# transmitter.net
KiCad netlist of a schematic drawn in EAGLE
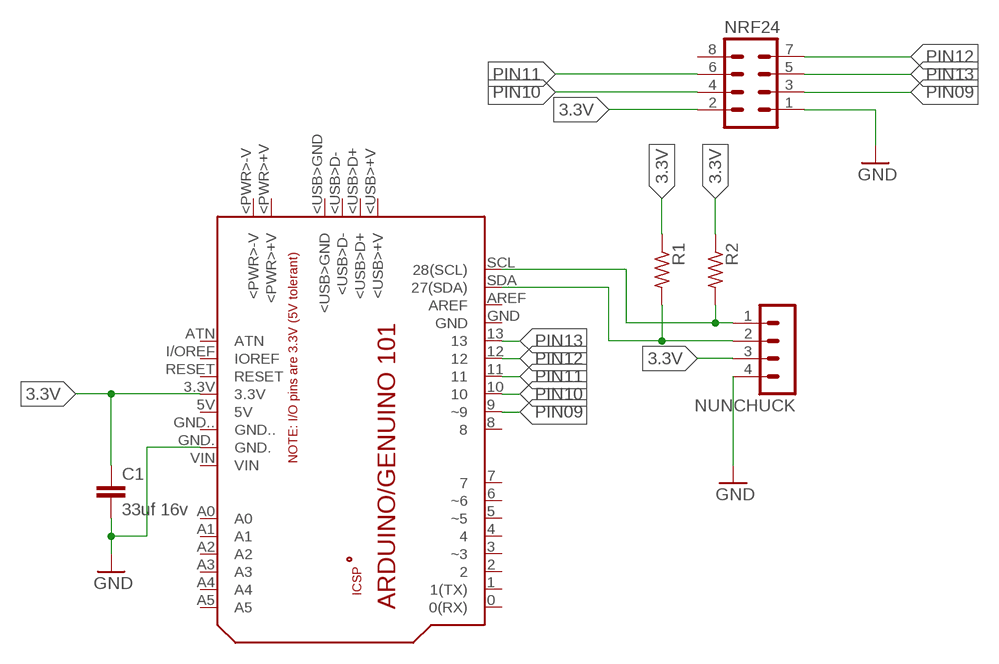
[diagram p0: schematic, sheet 1]

(export (version "E")
  (design (tool "Eeschema 10.0.6"))
  (components
    (comp (ref "C1")
      (value "33uf 16v")
      (footprint "eagle-import:C025-024X044")
      (libsource (lib "eagle-import") (part "C-EU025-024X044"))
    )
    (comp (ref "NRF24")
      (value "MA04-2")
      (footprint "eagle-import:MA04-2")
      (libsource (lib "eagle-import") (part "MA04-2"))
    )
    (comp (ref "NUNCHUCK")
      (value "MA04-1")
      (footprint "eagle-import:MA04-1")
      (libsource (lib "eagle-import") (part "MA04-1"))
    )
    (comp (ref "PCB1")
      (value "ARDUINO_101")
      (footprint "eagle-import:ARDUINO_101")
      (libsource (lib "eagle-import") (part "ARDUINO_101"))
    )
    (comp (ref "R1")
      (value "R-US_0204/2V")
      (footprint "eagle-import:0204V")
      (libsource (lib "eagle-import") (part "R-US_0204/2V"))
    )
    (comp (ref "R2")
      (value "R-US_0204/2V")
      (footprint "eagle-import:0204V")
      (libsource (lib "eagle-import") (part "R-US_0204/2V"))
    )
  )
  (nets
    (net (code "1") (name "3.3V") (class "Default")
      (node (ref "C1") (pin "1") (pinfunction "1_1") (pintype "passive"))
      (node (ref "NRF24") (pin "2") (pinfunction "2_2") (pintype "passive"))
      (node (ref "NUNCHUCK") (pin "3") (pinfunction "3_3") (pintype "passive"))
      (node (ref "PCB1") (pin "3.3V") (pinfunction "3.3V_3.3V") (pintype "bidirectional"))
      (node (ref "R1") (pin "1") (pinfunction "1_1") (pintype "passive"))
      (node (ref "R2") (pin "1") (pinfunction "1_1") (pintype "passive"))
    )
    (net (code "2") (name "GND") (class "Default")
      (node (ref "C1") (pin "2") (pinfunction "2_2") (pintype "passive"))
      (node (ref "NRF24") (pin "1") (pinfunction "1_1") (pintype "passive"))
      (node (ref "NUNCHUCK") (pin "4") (pinfunction "4_4") (pintype "passive"))
      (node (ref "PCB1") (pin "GND.") (pinfunction "GND._GND.") (pintype "bidirectional"))
    )
    (net (code "3") (name "Net-(PCB1-27(SDA))") (class "Default")
      (node (ref "NUNCHUCK") (pin "2") (pinfunction "2_2") (pintype "passive"))
      (node (ref "PCB1") (pin "SDA") (pinfunction "27(SDA)_SDA") (pintype "bidirectional"))
      (node (ref "R1") (pin "2") (pinfunction "2_2") (pintype "passive"))
    )
    (net (code "4") (name "Net-(PCB1-28(SCL))") (class "Default")
      (node (ref "NUNCHUCK") (pin "1") (pinfunction "1_1") (pintype "passive"))
      (node (ref "PCB1") (pin "SCL") (pinfunction "28(SCL)_SCL") (pintype "bidirectional"))
      (node (ref "R2") (pin "2") (pinfunction "2_2") (pintype "passive"))
    )
    (net (code "5") (name "PIN09") (class "Default")
      (node (ref "NRF24") (pin "3") (pinfunction "3_3") (pintype "passive"))
      (node (ref "PCB1") (pin "9") (pinfunction "~{9}_9") (pintype "bidirectional"))
    )
    (net (code "6") (name "PIN10") (class "Default")
      (node (ref "NRF24") (pin "4") (pinfunction "4_4") (pintype "passive"))
      (node (ref "PCB1") (pin "10") (pinfunction "10_10") (pintype "bidirectional"))
    )
    (net (code "7") (name "PIN11") (class "Default")
      (node (ref "NRF24") (pin "6") (pinfunction "6_6") (pintype "passive"))
      (node (ref "PCB1") (pin "11") (pinfunction "11_11") (pintype "bidirectional"))
    )
    (net (code "8") (name "PIN12") (class "Default")
      (node (ref "NRF24") (pin "7") (pinfunction "7_7") (pintype "passive"))
      (node (ref "PCB1") (pin "12") (pinfunction "12_12") (pintype "bidirectional"))
    )
    (net (code "9") (name "PIN13") (class "Default")
      (node (ref "NRF24") (pin "5") (pinfunction "5_5") (pintype "passive"))
      (node (ref "PCB1") (pin "13") (pinfunction "13_13") (pintype "bidirectional"))
    )
    (net (code "10") (name "unconnected-(NRF24-Pad8)") (class "Default")
      (node (ref "NRF24") (pin "8") (pinfunction "8_8") (pintype "passive"))
    )
    (net (code "11") (name "unconnected-(PCB1-0(RX)-Pad0)") (class "Default")
      (node (ref "PCB1") (pin "0") (pinfunction "0(RX)_0") (pintype "bidirectional"))
    )
    (net (code "12") (name "unconnected-(PCB1-1(TX)-Pad1)") (class "Default")
      (node (ref "PCB1") (pin "1") (pinfunction "1(TX)_1") (pintype "bidirectional"))
    )
    (net (code "13") (name "unconnected-(PCB1-IOREF-PadI{slash}OREF)") (class "Default")
      (node (ref "PCB1") (pin "I/OREF") (pinfunction "IOREF_I/OREF") (pintype "bidirectional"))
    )
    (net (code "14") (name "unconnected-(PCB1-Pad+5V)") (class "Default")
      (node (ref "PCB1") (pin "+5V") (pinfunction "+5V_+5V") (pintype "bidirectional"))
    )
    (net (code "15") (name "unconnected-(PCB1-Pad2)") (class "Default")
      (node (ref "PCB1") (pin "2") (pinfunction "2_2") (pintype "bidirectional"))
    )
    (net (code "16") (name "unconnected-(PCB1-Pad4)") (class "Default")
      (node (ref "PCB1") (pin "4") (pinfunction "4_4") (pintype "bidirectional"))
    )
    (net (code "17") (name "unconnected-(PCB1-Pad5V)") (class "Default")
      (node (ref "PCB1") (pin "5V") (pinfunction "5V_5V") (pintype "bidirectional"))
    )
    (net (code "18") (name "unconnected-(PCB1-Pad7)") (class "Default")
      (node (ref "PCB1") (pin "7") (pinfunction "7_7") (pintype "bidirectional"))
    )
    (net (code "19") (name "unconnected-(PCB1-Pad8)") (class "Default")
      (node (ref "PCB1") (pin "8") (pinfunction "8_8") (pintype "bidirectional"))
    )
    (net (code "20") (name "unconnected-(PCB1-Pad<PWR>+V)") (class "Default")
      (node (ref "PCB1") (pin "<PWR>+V") (pinfunction "<PWR>+V_<PWR>+V") (pintype "bidirectional"))
    )
    (net (code "21") (name "unconnected-(PCB1-Pad<PWR>-V)") (class "Default")
      (node (ref "PCB1") (pin "<PWR>-V") (pinfunction "<PWR>-V_<PWR>-V") (pintype "bidirectional"))
    )
    (net (code "22") (name "unconnected-(PCB1-Pad<USB>+V)") (class "Default")
      (node (ref "PCB1") (pin "<USB>+V") (pinfunction "<USB>+V_<USB>+V") (pintype "bidirectional"))
    )
    (net (code "23") (name "unconnected-(PCB1-Pad<USB>D+)") (class "Default")
      (node (ref "PCB1") (pin "<USB>D+") (pinfunction "<USB>D+_<USB>D+") (pintype "bidirectional"))
    )
    (net (code "24") (name "unconnected-(PCB1-Pad<USB>D-)") (class "Default")
      (node (ref "PCB1") (pin "<USB>D-") (pinfunction "<USB>D-_<USB>D-") (pintype "bidirectional"))
    )
    (net (code "25") (name "unconnected-(PCB1-Pad<USB>GND)") (class "Default")
      (node (ref "PCB1") (pin "<USB>GND") (pinfunction "<USB>GND_<USB>GND") (pintype "bidirectional"))
    )
    (net (code "26") (name "unconnected-(PCB1-PadA0)") (class "Default")
      (node (ref "PCB1") (pin "A0") (pinfunction "A0_A0") (pintype "bidirectional"))
    )
    (net (code "27") (name "unconnected-(PCB1-PadA1)") (class "Default")
      (node (ref "PCB1") (pin "A1") (pinfunction "A1_A1") (pintype "bidirectional"))
    )
    (net (code "28") (name "unconnected-(PCB1-PadA2)") (class "Default")
      (node (ref "PCB1") (pin "A2") (pinfunction "A2_A2") (pintype "bidirectional"))
    )
    (net (code "29") (name "unconnected-(PCB1-PadA3)") (class "Default")
      (node (ref "PCB1") (pin "A3") (pinfunction "A3_A3") (pintype "bidirectional"))
    )
    (net (code "30") (name "unconnected-(PCB1-PadA4)") (class "Default")
      (node (ref "PCB1") (pin "A4") (pinfunction "A4_A4") (pintype "bidirectional"))
    )
    (net (code "31") (name "unconnected-(PCB1-PadA5)") (class "Default")
      (node (ref "PCB1") (pin "A5") (pinfunction "A5_A5") (pintype "bidirectional"))
    )
    (net (code "32") (name "unconnected-(PCB1-PadAREF)") (class "Default")
      (node (ref "PCB1") (pin "AREF") (pinfunction "AREF_AREF") (pintype "bidirectional"))
    )
    (net (code "33") (name "unconnected-(PCB1-PadATN)") (class "Default")
      (node (ref "PCB1") (pin "ATN") (pinfunction "ATN_ATN") (pintype "bidirectional"))
    )
    (net (code "34") (name "unconnected-(PCB1-PadGND)") (class "Default")
      (node (ref "PCB1") (pin "GND") (pinfunction "GND_GND") (pintype "bidirectional"))
    )
    (net (code "35") (name "unconnected-(PCB1-PadGND..)") (class "Default")
      (node (ref "PCB1") (pin "GND..") (pinfunction "GND.._GND..") (pintype "bidirectional"))
    )
    (net (code "36") (name "unconnected-(PCB1-PadGND_)") (class "Default")
      (node (ref "PCB1") (pin "GND_") (pinfunction "GND__GND_") (pintype "bidirectional"))
    )
    (net (code "37") (name "unconnected-(PCB1-PadMISO)") (class "Default")
      (node (ref "PCB1") (pin "MISO") (pinfunction "MISO_MISO") (pintype "bidirectional"))
    )
    (net (code "38") (name "unconnected-(PCB1-PadMOSI)") (class "Default")
      (node (ref "PCB1") (pin "MOSI") (pinfunction "MOSI_MOSI") (pintype "bidirectional"))
    )
    (net (code "39") (name "unconnected-(PCB1-PadRESET)") (class "Default")
      (node (ref "PCB1") (pin "RESET") (pinfunction "RESET_RESET") (pintype "bidirectional"))
    )
    (net (code "40") (name "unconnected-(PCB1-PadRESET.)") (class "Default")
      (node (ref "PCB1") (pin "RESET.") (pinfunction "RESET._RESET.") (pintype "bidirectional"))
    )
    (net (code "41") (name "unconnected-(PCB1-PadSCK)") (class "Default")
      (node (ref "PCB1") (pin "SCK") (pinfunction "SCK_SCK") (pintype "bidirectional"))
    )
    (net (code "42") (name "unconnected-(PCB1-PadVIN)") (class "Default")
      (node (ref "PCB1") (pin "VIN") (pinfunction "VIN_VIN") (pintype "bidirectional"))
    )
    (net (code "43") (name "unconnected-(PCB1-~{3}-Pad3)") (class "Default")
      (node (ref "PCB1") (pin "3") (pinfunction "~{3}_3") (pintype "bidirectional"))
    )
    (net (code "44") (name "unconnected-(PCB1-~{5}-Pad5)") (class "Default")
      (node (ref "PCB1") (pin "5") (pinfunction "~{5}_5") (pintype "bidirectional"))
    )
    (net (code "45") (name "unconnected-(PCB1-~{6}-Pad6)") (class "Default")
      (node (ref "PCB1") (pin "6") (pinfunction "~{6}_6") (pintype "bidirectional"))
    )
  )
)
